# Hera_v1.net
KiCad netlist of a schematic drawn in EAGLE
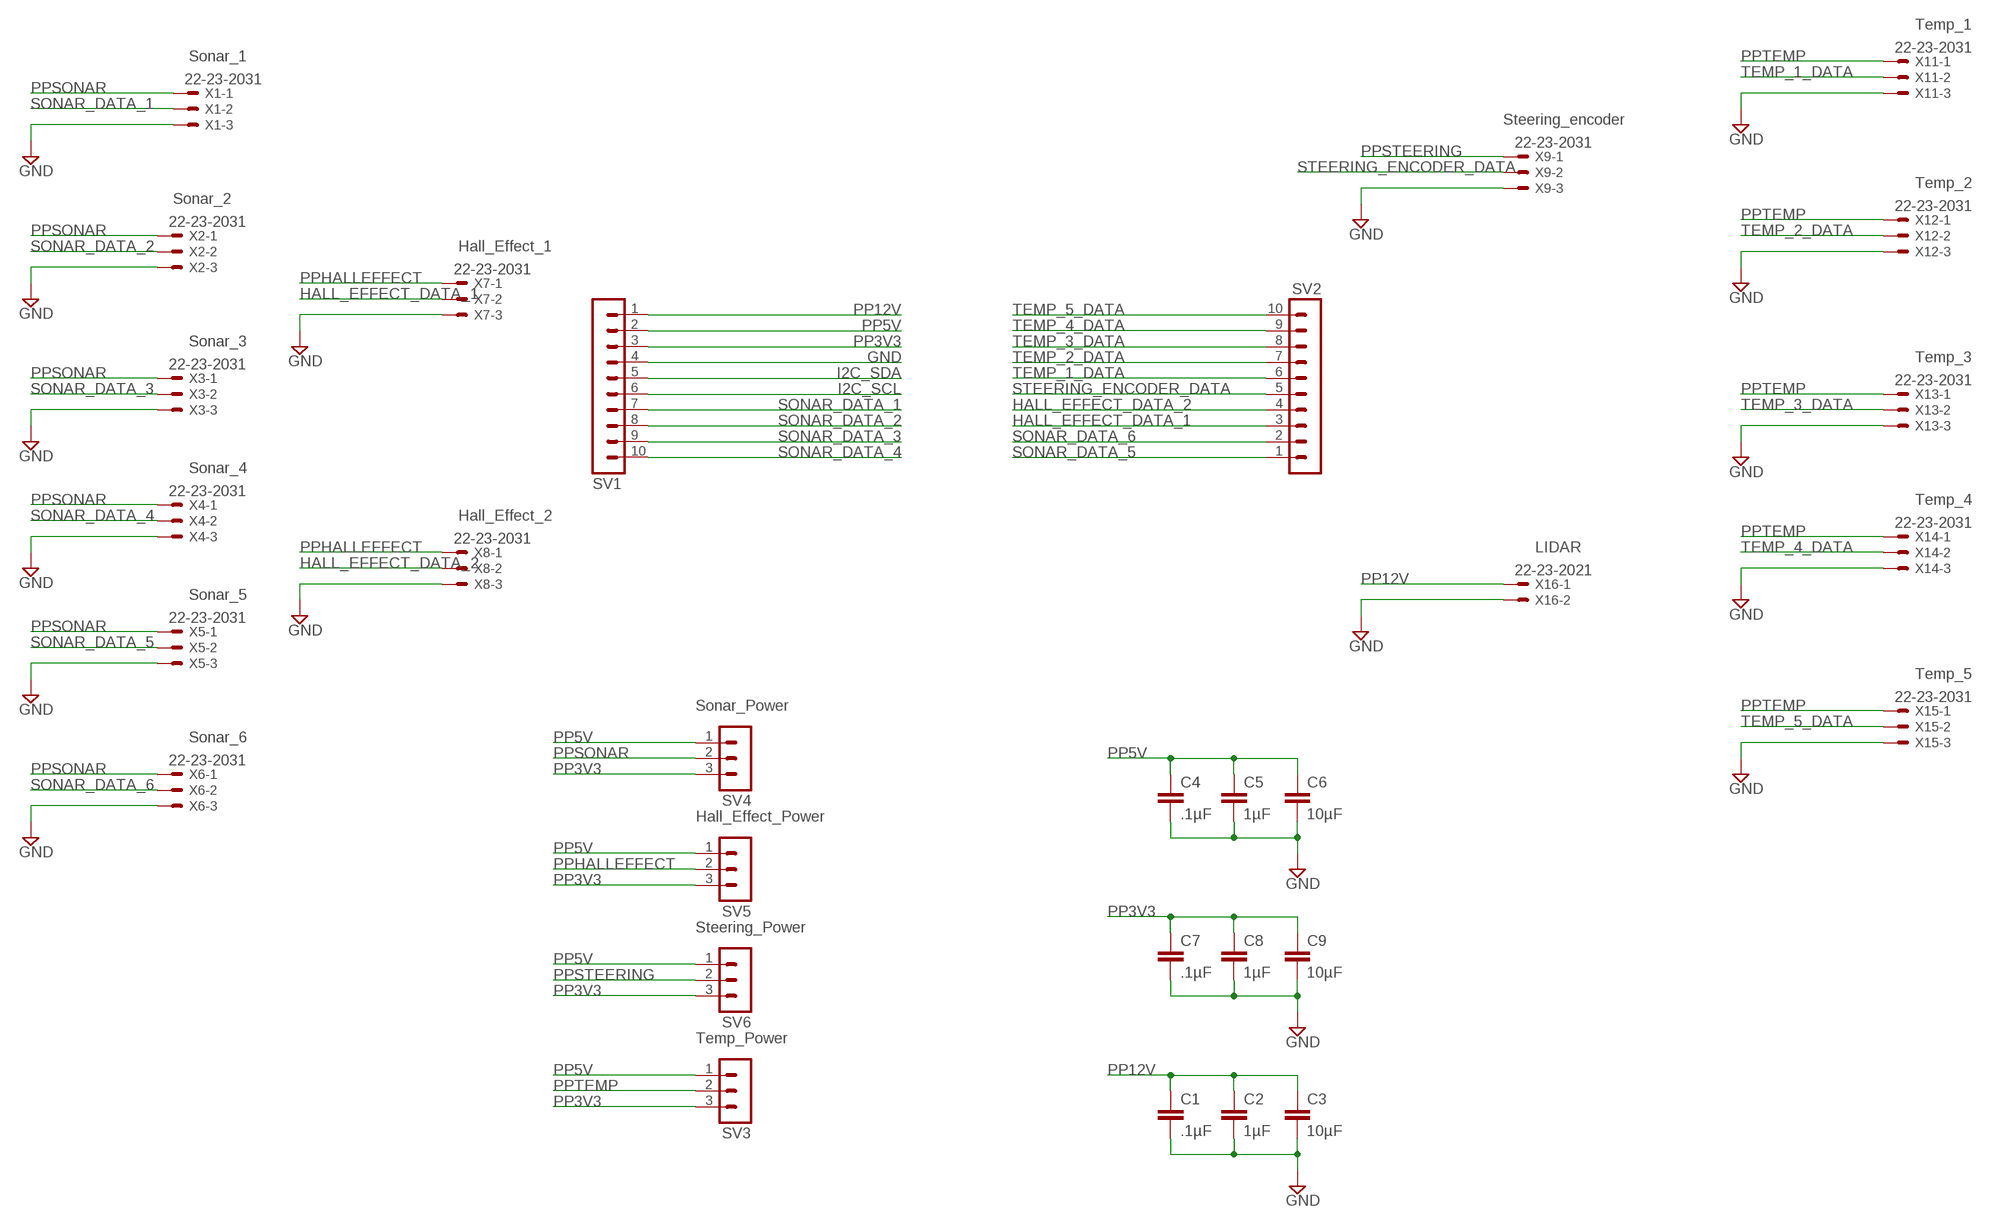
[diagram p0: schematic, sheet 1]

(export (version "E")
  (design (tool "Eeschema 10.0.6"))
  (components
    (comp (ref "C1")
      (value ".1µF")
      (footprint "eagle-import:C0402")
      (libsource (lib "eagle-import") (part "C-EUC0402"))
    )
    (comp (ref "C2")
      (value "1µF")
      (footprint "eagle-import:C0603")
      (libsource (lib "eagle-import") (part "C-EUC0603"))
    )
    (comp (ref "C3")
      (value "10µF")
      (footprint "eagle-import:C1206")
      (libsource (lib "eagle-import") (part "C-EUC1206"))
    )
    (comp (ref "C4")
      (value ".1µF")
      (footprint "eagle-import:C0402")
      (libsource (lib "eagle-import") (part "C-EUC0402"))
    )
    (comp (ref "C5")
      (value "1µF")
      (footprint "eagle-import:C0603")
      (libsource (lib "eagle-import") (part "C-EUC0603"))
    )
    (comp (ref "C6")
      (value "10µF")
      (footprint "eagle-import:C1206")
      (libsource (lib "eagle-import") (part "C-EUC1206"))
    )
    (comp (ref "C7")
      (value ".1µF")
      (footprint "eagle-import:C0402")
      (libsource (lib "eagle-import") (part "C-EUC0402"))
    )
    (comp (ref "C8")
      (value "1µF")
      (footprint "eagle-import:C0603")
      (libsource (lib "eagle-import") (part "C-EUC0603"))
    )
    (comp (ref "C9")
      (value "10µF")
      (footprint "eagle-import:C1206")
      (libsource (lib "eagle-import") (part "C-EUC1206"))
    )
    (comp (ref "SV1")
      (value "MA10-1")
      (footprint "eagle-import:MA10-1")
      (libsource (lib "eagle-import") (part "MA10-1"))
    )
    (comp (ref "SV2")
      (value "MA10-1")
      (footprint "eagle-import:MA10-1")
      (libsource (lib "eagle-import") (part "MA10-1"))
    )
    (comp (ref "SV3")
      (value "MA03-1")
      (footprint "eagle-import:MA03-1")
      (libsource (lib "eagle-import") (part "MA03-1"))
    )
    (comp (ref "SV4")
      (value "MA03-1")
      (footprint "eagle-import:MA03-1")
      (libsource (lib "eagle-import") (part "MA03-1"))
    )
    (comp (ref "SV5")
      (value "MA03-1")
      (footprint "eagle-import:MA03-1")
      (libsource (lib "eagle-import") (part "MA03-1"))
    )
    (comp (ref "SV6")
      (value "MA03-1")
      (footprint "eagle-import:MA03-1")
      (libsource (lib "eagle-import") (part "MA03-1"))
    )
    (comp (ref "X1")
      (value "22-23-2031")
      (footprint "eagle-import:22-23-2031")
      (fields (field (name "MF") "MOLEX"))
      (libsource (lib "eagle-import") (part "22-23-2031"))
    )
    (comp (ref "X2")
      (value "22-23-2031")
      (footprint "eagle-import:22-23-2031")
      (fields (field (name "MF") "MOLEX"))
      (libsource (lib "eagle-import") (part "22-23-2031"))
    )
    (comp (ref "X3")
      (value "22-23-2031")
      (footprint "eagle-import:22-23-2031")
      (fields (field (name "MF") "MOLEX"))
      (libsource (lib "eagle-import") (part "22-23-2031"))
    )
    (comp (ref "X4")
      (value "22-23-2031")
      (footprint "eagle-import:22-23-2031")
      (fields (field (name "MF") "MOLEX"))
      (libsource (lib "eagle-import") (part "22-23-2031"))
    )
    (comp (ref "X5")
      (value "22-23-2031")
      (footprint "eagle-import:22-23-2031")
      (fields (field (name "MF") "MOLEX"))
      (libsource (lib "eagle-import") (part "22-23-2031"))
    )
    (comp (ref "X6")
      (value "22-23-2031")
      (footprint "eagle-import:22-23-2031")
      (fields (field (name "MF") "MOLEX"))
      (libsource (lib "eagle-import") (part "22-23-2031"))
    )
    (comp (ref "X7")
      (value "22-23-2031")
      (footprint "eagle-import:22-23-2031")
      (fields (field (name "MF") "MOLEX"))
      (libsource (lib "eagle-import") (part "22-23-2031"))
    )
    (comp (ref "X8")
      (value "22-23-2031")
      (footprint "eagle-import:22-23-2031")
      (fields (field (name "MF") "MOLEX"))
      (libsource (lib "eagle-import") (part "22-23-2031"))
    )
    (comp (ref "X9")
      (value "22-23-2031")
      (footprint "eagle-import:22-23-2031")
      (fields (field (name "MF") "MOLEX"))
      (libsource (lib "eagle-import") (part "22-23-2031"))
    )
    (comp (ref "X11")
      (value "22-23-2031")
      (footprint "eagle-import:22-23-2031")
      (fields (field (name "MF") "MOLEX"))
      (libsource (lib "eagle-import") (part "22-23-2031"))
    )
    (comp (ref "X12")
      (value "22-23-2031")
      (footprint "eagle-import:22-23-2031")
      (fields (field (name "MF") "MOLEX"))
      (libsource (lib "eagle-import") (part "22-23-2031"))
    )
    (comp (ref "X13")
      (value "22-23-2031")
      (footprint "eagle-import:22-23-2031")
      (fields (field (name "MF") "MOLEX"))
      (libsource (lib "eagle-import") (part "22-23-2031"))
    )
    (comp (ref "X14")
      (value "22-23-2031")
      (footprint "eagle-import:22-23-2031")
      (fields (field (name "MF") "MOLEX"))
      (libsource (lib "eagle-import") (part "22-23-2031"))
    )
    (comp (ref "X15")
      (value "22-23-2031")
      (footprint "eagle-import:22-23-2031")
      (fields (field (name "MF") "MOLEX"))
      (libsource (lib "eagle-import") (part "22-23-2031"))
    )
    (comp (ref "X16")
      (value "22-23-2021")
      (footprint "eagle-import:22-23-2021")
      (fields (field (name "MF") "MOLEX"))
      (libsource (lib "eagle-import") (part "22-23-2021"))
    )
  )
  (nets
    (net (code "1") (name "/HALL_EFFECT_DATA_1") (class "Default")
      (node (ref "SV2") (pin "3") (pinfunction "3_3") (pintype "passive"))
      (node (ref "X7") (pin "2") (pinfunction "S_2") (pintype "passive"))
    )
    (net (code "2") (name "/HALL_EFFECT_DATA_2") (class "Default")
      (node (ref "SV2") (pin "4") (pinfunction "4_4") (pintype "passive"))
      (node (ref "X8") (pin "2") (pinfunction "S_2") (pintype "passive"))
    )
    (net (code "3") (name "/I2C_SCL") (class "Default")
      (node (ref "SV1") (pin "6") (pinfunction "6_6") (pintype "passive"))
    )
    (net (code "4") (name "/I2C_SDA") (class "Default")
      (node (ref "SV1") (pin "5") (pinfunction "5_5") (pintype "passive"))
    )
    (net (code "5") (name "/PP3V3") (class "Default")
      (node (ref "C7") (pin "1") (pinfunction "1_1") (pintype "passive"))
      (node (ref "C8") (pin "1") (pinfunction "1_1") (pintype "passive"))
      (node (ref "C9") (pin "1") (pinfunction "1_1") (pintype "passive"))
      (node (ref "SV1") (pin "3") (pinfunction "3_3") (pintype "passive"))
      (node (ref "SV3") (pin "3") (pinfunction "3_3") (pintype "passive"))
      (node (ref "SV4") (pin "3") (pinfunction "3_3") (pintype "passive"))
      (node (ref "SV5") (pin "3") (pinfunction "3_3") (pintype "passive"))
      (node (ref "SV6") (pin "3") (pinfunction "3_3") (pintype "passive"))
    )
    (net (code "6") (name "/PP5V") (class "Default")
      (node (ref "C4") (pin "1") (pinfunction "1_1") (pintype "passive"))
      (node (ref "C5") (pin "1") (pinfunction "1_1") (pintype "passive"))
      (node (ref "C6") (pin "1") (pinfunction "1_1") (pintype "passive"))
      (node (ref "SV1") (pin "2") (pinfunction "2_2") (pintype "passive"))
      (node (ref "SV3") (pin "1") (pinfunction "1_1") (pintype "passive"))
      (node (ref "SV4") (pin "1") (pinfunction "1_1") (pintype "passive"))
      (node (ref "SV5") (pin "1") (pinfunction "1_1") (pintype "passive"))
      (node (ref "SV6") (pin "1") (pinfunction "1_1") (pintype "passive"))
    )
    (net (code "7") (name "/PP12V") (class "Default")
      (node (ref "C1") (pin "1") (pinfunction "1_1") (pintype "passive"))
      (node (ref "C2") (pin "1") (pinfunction "1_1") (pintype "passive"))
      (node (ref "C3") (pin "1") (pinfunction "1_1") (pintype "passive"))
      (node (ref "SV1") (pin "1") (pinfunction "1_1") (pintype "passive"))
      (node (ref "X16") (pin "1") (pinfunction "S_1") (pintype "passive"))
    )
    (net (code "8") (name "/PPHALLEFFECT") (class "Default")
      (node (ref "SV5") (pin "2") (pinfunction "2_2") (pintype "passive"))
      (node (ref "X7") (pin "1") (pinfunction "S_1") (pintype "passive"))
      (node (ref "X8") (pin "1") (pinfunction "S_1") (pintype "passive"))
    )
    (net (code "9") (name "/PPSONAR") (class "Default")
      (node (ref "SV4") (pin "2") (pinfunction "2_2") (pintype "passive"))
      (node (ref "X1") (pin "1") (pinfunction "S_1") (pintype "passive"))
      (node (ref "X2") (pin "1") (pinfunction "S_1") (pintype "passive"))
      (node (ref "X3") (pin "1") (pinfunction "S_1") (pintype "passive"))
      (node (ref "X4") (pin "1") (pinfunction "S_1") (pintype "passive"))
      (node (ref "X5") (pin "1") (pinfunction "S_1") (pintype "passive"))
      (node (ref "X6") (pin "1") (pinfunction "S_1") (pintype "passive"))
    )
    (net (code "10") (name "/PPSTEERING") (class "Default")
      (node (ref "SV6") (pin "2") (pinfunction "2_2") (pintype "passive"))
      (node (ref "X9") (pin "1") (pinfunction "S_1") (pintype "passive"))
    )
    (net (code "11") (name "/PPTEMP") (class "Default")
      (node (ref "SV3") (pin "2") (pinfunction "2_2") (pintype "passive"))
      (node (ref "X11") (pin "1") (pinfunction "S_1") (pintype "passive"))
      (node (ref "X12") (pin "1") (pinfunction "S_1") (pintype "passive"))
      (node (ref "X13") (pin "1") (pinfunction "S_1") (pintype "passive"))
      (node (ref "X14") (pin "1") (pinfunction "S_1") (pintype "passive"))
      (node (ref "X15") (pin "1") (pinfunction "S_1") (pintype "passive"))
    )
    (net (code "12") (name "/SONAR_DATA_1") (class "Default")
      (node (ref "SV1") (pin "7") (pinfunction "7_7") (pintype "passive"))
      (node (ref "X1") (pin "2") (pinfunction "S_2") (pintype "passive"))
    )
    (net (code "13") (name "/SONAR_DATA_2") (class "Default")
      (node (ref "SV1") (pin "8") (pinfunction "8_8") (pintype "passive"))
      (node (ref "X2") (pin "2") (pinfunction "S_2") (pintype "passive"))
    )
    (net (code "14") (name "/SONAR_DATA_3") (class "Default")
      (node (ref "SV1") (pin "9") (pinfunction "9_9") (pintype "passive"))
      (node (ref "X3") (pin "2") (pinfunction "S_2") (pintype "passive"))
    )
    (net (code "15") (name "/SONAR_DATA_4") (class "Default")
      (node (ref "SV1") (pin "10") (pinfunction "10_10") (pintype "passive"))
      (node (ref "X4") (pin "2") (pinfunction "S_2") (pintype "passive"))
    )
    (net (code "16") (name "/SONAR_DATA_5") (class "Default")
      (node (ref "SV2") (pin "1") (pinfunction "1_1") (pintype "passive"))
      (node (ref "X5") (pin "2") (pinfunction "S_2") (pintype "passive"))
    )
    (net (code "17") (name "/SONAR_DATA_6") (class "Default")
      (node (ref "SV2") (pin "2") (pinfunction "2_2") (pintype "passive"))
      (node (ref "X6") (pin "2") (pinfunction "S_2") (pintype "passive"))
    )
    (net (code "18") (name "/STEERING_ENCODER_DATA") (class "Default")
      (node (ref "SV2") (pin "5") (pinfunction "5_5") (pintype "passive"))
      (node (ref "X9") (pin "2") (pinfunction "S_2") (pintype "passive"))
    )
    (net (code "19") (name "/TEMP_1_DATA") (class "Default")
      (node (ref "SV2") (pin "6") (pinfunction "6_6") (pintype "passive"))
      (node (ref "X11") (pin "2") (pinfunction "S_2") (pintype "passive"))
    )
    (net (code "20") (name "/TEMP_2_DATA") (class "Default")
      (node (ref "SV2") (pin "7") (pinfunction "7_7") (pintype "passive"))
      (node (ref "X12") (pin "2") (pinfunction "S_2") (pintype "passive"))
    )
    (net (code "21") (name "/TEMP_3_DATA") (class "Default")
      (node (ref "SV2") (pin "8") (pinfunction "8_8") (pintype "passive"))
      (node (ref "X13") (pin "2") (pinfunction "S_2") (pintype "passive"))
    )
    (net (code "22") (name "/TEMP_4_DATA") (class "Default")
      (node (ref "SV2") (pin "9") (pinfunction "9_9") (pintype "passive"))
      (node (ref "X14") (pin "2") (pinfunction "S_2") (pintype "passive"))
    )
    (net (code "23") (name "/TEMP_5_DATA") (class "Default")
      (node (ref "SV2") (pin "10") (pinfunction "10_10") (pintype "passive"))
      (node (ref "X15") (pin "2") (pinfunction "S_2") (pintype "passive"))
    )
    (net (code "24") (name "GND") (class "Default")
      (node (ref "C1") (pin "2") (pinfunction "2_2") (pintype "passive"))
      (node (ref "C2") (pin "2") (pinfunction "2_2") (pintype "passive"))
      (node (ref "C3") (pin "2") (pinfunction "2_2") (pintype "passive"))
      (node (ref "C4") (pin "2") (pinfunction "2_2") (pintype "passive"))
      (node (ref "C5") (pin "2") (pinfunction "2_2") (pintype "passive"))
      (node (ref "C6") (pin "2") (pinfunction "2_2") (pintype "passive"))
      (node (ref "C7") (pin "2") (pinfunction "2_2") (pintype "passive"))
      (node (ref "C8") (pin "2") (pinfunction "2_2") (pintype "passive"))
      (node (ref "C9") (pin "2") (pinfunction "2_2") (pintype "passive"))
      (node (ref "SV1") (pin "4") (pinfunction "4_4") (pintype "passive"))
      (node (ref "X1") (pin "3") (pinfunction "S_3") (pintype "passive"))
      (node (ref "X11") (pin "3") (pinfunction "S_3") (pintype "passive"))
      (node (ref "X12") (pin "3") (pinfunction "S_3") (pintype "passive"))
      (node (ref "X13") (pin "3") (pinfunction "S_3") (pintype "passive"))
      (node (ref "X14") (pin "3") (pinfunction "S_3") (pintype "passive"))
      (node (ref "X15") (pin "3") (pinfunction "S_3") (pintype "passive"))
      (node (ref "X16") (pin "2") (pinfunction "S_2") (pintype "passive"))
      (node (ref "X2") (pin "3") (pinfunction "S_3") (pintype "passive"))
      (node (ref "X3") (pin "3") (pinfunction "S_3") (pintype "passive"))
      (node (ref "X4") (pin "3") (pinfunction "S_3") (pintype "passive"))
      (node (ref "X5") (pin "3") (pinfunction "S_3") (pintype "passive"))
      (node (ref "X6") (pin "3") (pinfunction "S_3") (pintype "passive"))
      (node (ref "X7") (pin "3") (pinfunction "S_3") (pintype "passive"))
      (node (ref "X8") (pin "3") (pinfunction "S_3") (pintype "passive"))
      (node (ref "X9") (pin "3") (pinfunction "S_3") (pintype "passive"))
    )
  )
)
